# Main.net
KiCad netlist of a schematic drawn in Altium Designer
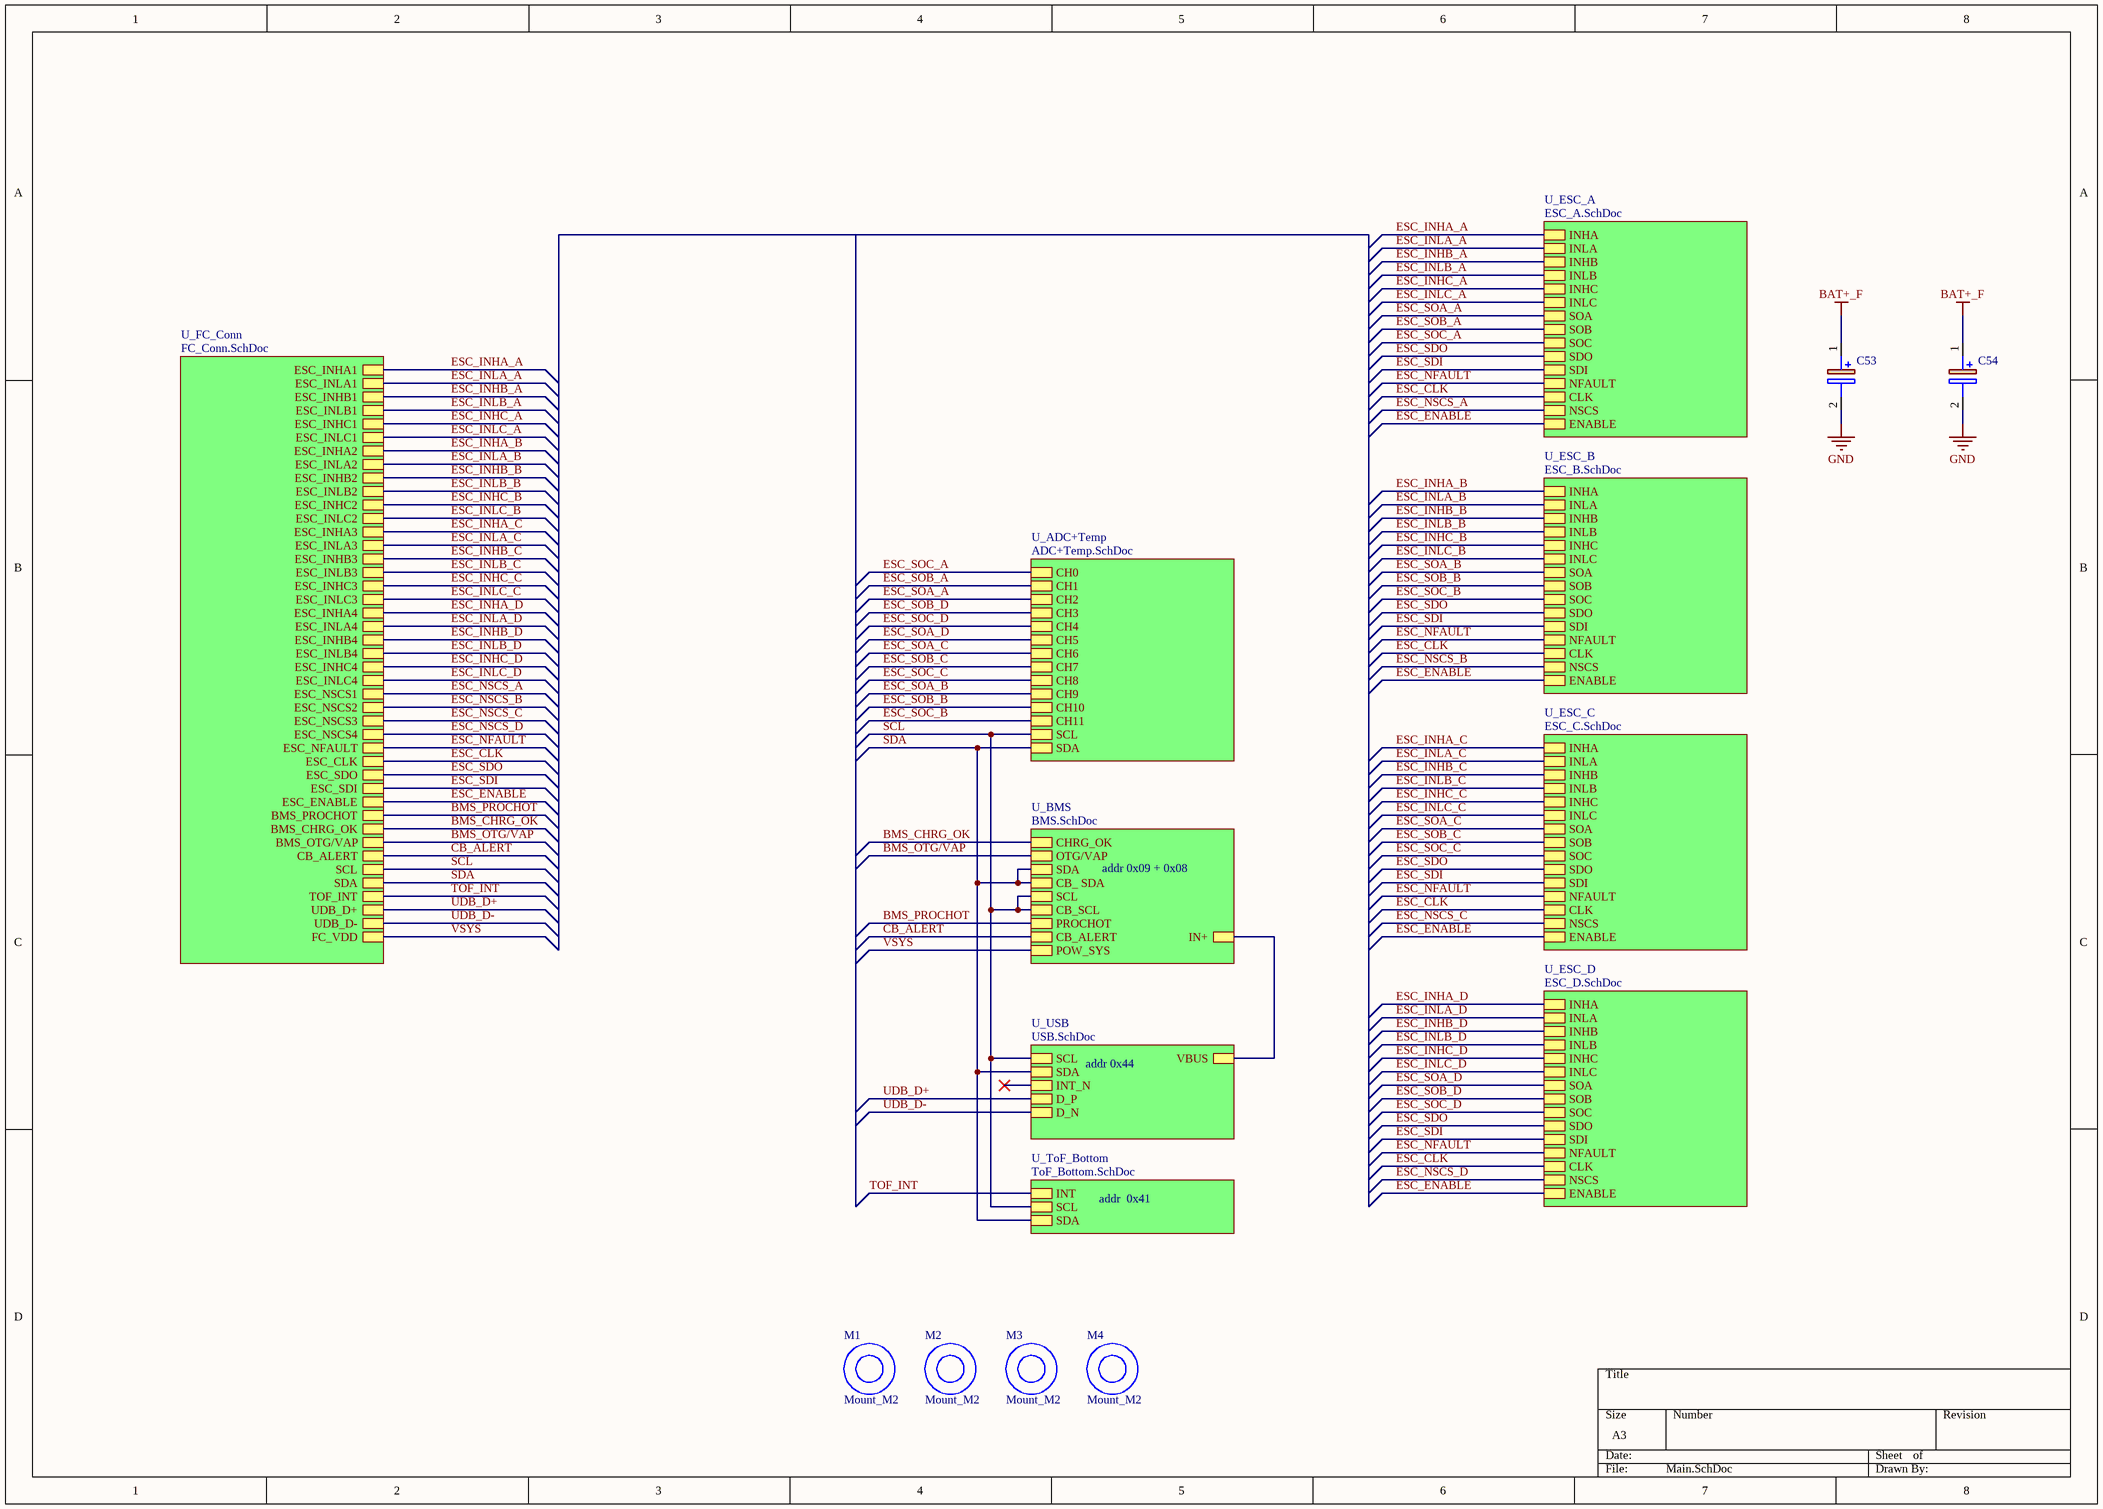
[diagram p0: Main.SchDoc]

(export (version "E")
  (design (tool "Eeschema 10.0.6"))
  (components
    (comp (ref "C53")
      (value "EEH-ZL1V151XP")
      (footprint "SamacSys:EEEHP1H4R7P")
      (description "Capacitor Polarised")
      (libsource (lib "*") (part "EEH-ZL1V151XP"))
    )
    (comp (ref "C54")
      (value "EEH-ZL1V151XP")
      (footprint "SamacSys:EEEHP1H4R7P")
      (description "Capacitor Polarised")
      (libsource (lib "*") (part "EEH-ZL1V151XP"))
    )
    (comp (ref "M1")
      (value "Mount_M2")
      (footprint "SamacSys:Mount_M2")
      (libsource (lib "SamacSys") (part "Mount_M2"))
    )
    (comp (ref "M2")
      (value "Mount_M2")
      (footprint "SamacSys:Mount_M2")
      (libsource (lib "SamacSys") (part "Mount_M2"))
    )
    (comp (ref "M3")
      (value "Mount_M2")
      (footprint "SamacSys:Mount_M2")
      (libsource (lib "SamacSys") (part "Mount_M2"))
    )
    (comp (ref "M4")
      (value "Mount_M2")
      (footprint "SamacSys:Mount_M2")
      (libsource (lib "SamacSys") (part "Mount_M2"))
    )
  )
  (nets
    (net (code "58") (name "BAT+_F") (class "Default")
      (node (ref "C53") (pin "1") (pinfunction "+_1") (pintype "passive"))
      (node (ref "C54") (pin "1") (pinfunction "+_1") (pintype "passive"))
    )
    (net (code "59") (name "GND") (class "Default")
      (node (ref "C53") (pin "2") (pinfunction "-_2") (pintype "passive"))
      (node (ref "C54") (pin "2") (pinfunction "-_2") (pintype "passive"))
    )
  )
)
